# Simple_MCU_V01.net
KiCad netlist of a schematic drawn in EAGLE
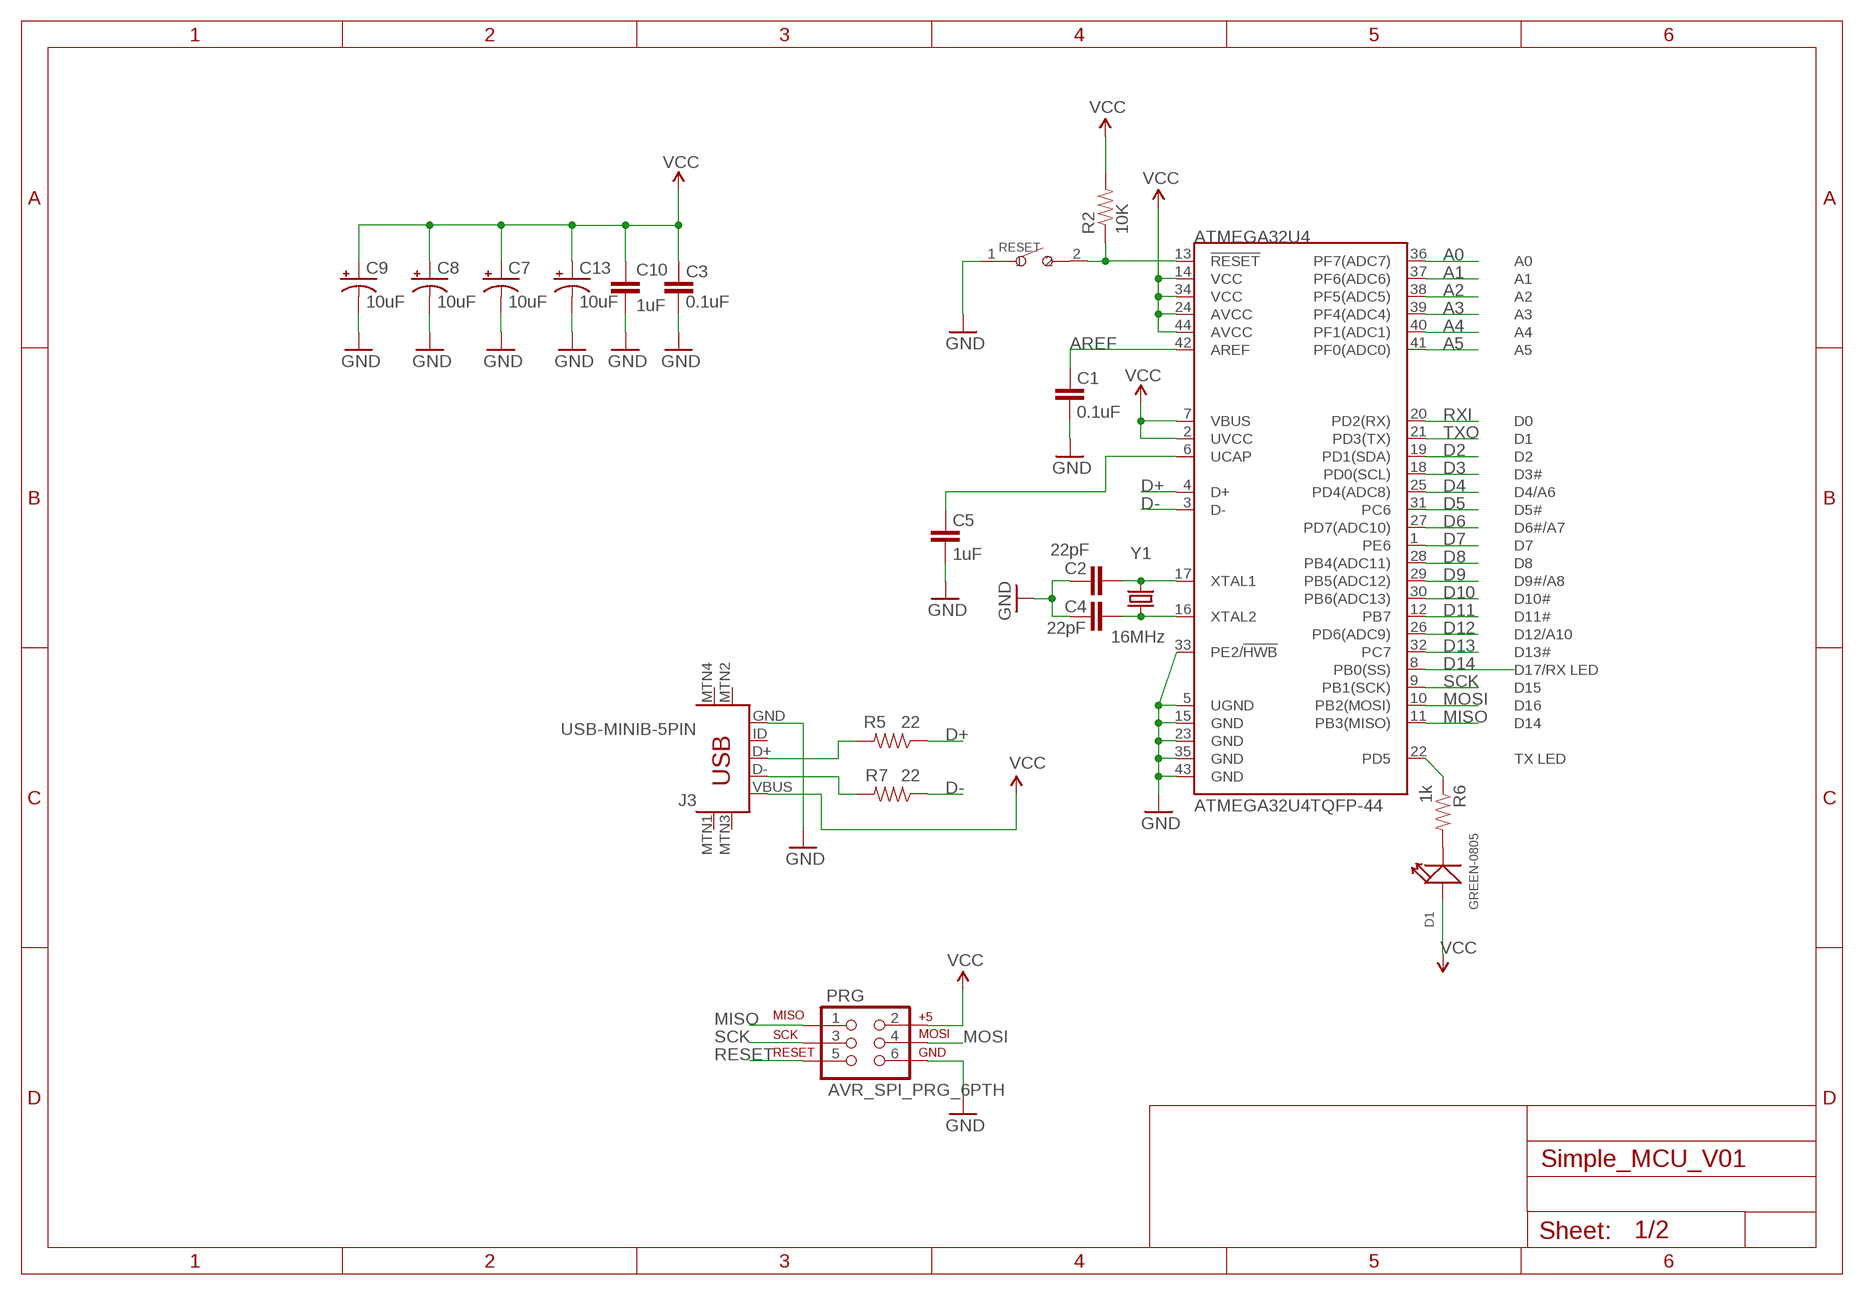
[diagram p0: schematic, sheet 1]
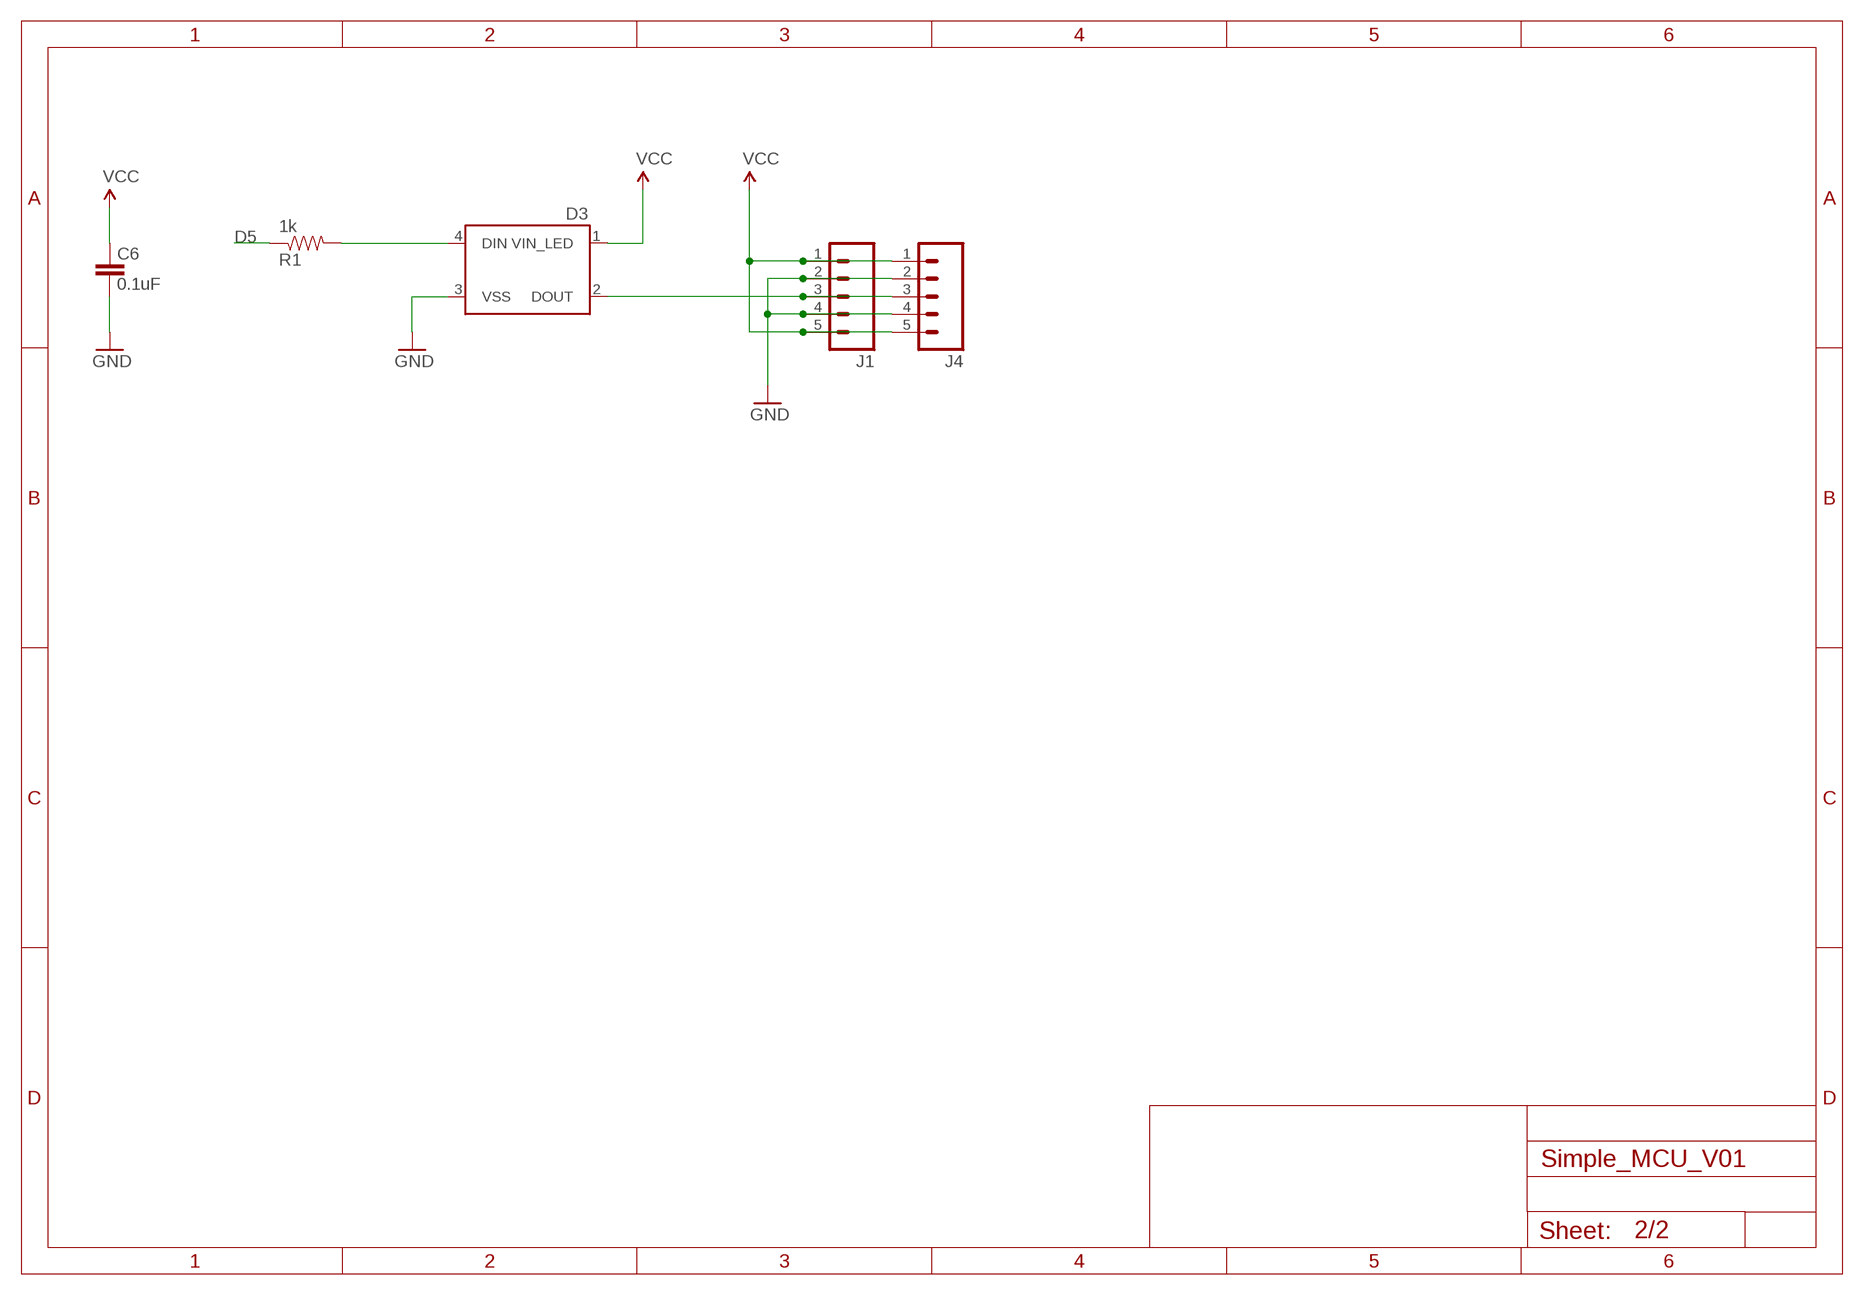
[diagram p1: schematic, sheet 2]

(export (version "E")
  (design (tool "Eeschema 10.0.6"))
  (components
    (comp (ref "ATMEGA32U4")
      (value "ATMEGA32U4TQFP-44")
      (footprint "eagle-import:TQFP44")
      (libsource (lib "eagle-import") (part "ATMEGA32U4TQFP-44"))
    )
    (comp (ref "C1")
      (value "0.1uF")
      (footprint "eagle-import:0805")
      (libsource (lib "eagle-import") (part "CAP0805"))
    )
    (comp (ref "C2")
      (value "22pF")
      (footprint "eagle-import:0805")
      (libsource (lib "eagle-import") (part "CAP0805"))
    )
    (comp (ref "C3")
      (value "0.1uF")
      (footprint "eagle-import:0805")
      (libsource (lib "eagle-import") (part "CAP0805"))
    )
    (comp (ref "C4")
      (value "22pF")
      (footprint "eagle-import:0805")
      (libsource (lib "eagle-import") (part "CAP0805"))
    )
    (comp (ref "C5")
      (value "1uF")
      (footprint "eagle-import:0805")
      (libsource (lib "eagle-import") (part "CAP0805"))
    )
    (comp (ref "C7")
      (value "10uF")
      (footprint "eagle-import:EIA3216")
      (libsource (lib "eagle-import") (part "CAP_POL1206"))
    )
    (comp (ref "C8")
      (value "10uF")
      (footprint "eagle-import:EIA3216")
      (libsource (lib "eagle-import") (part "CAP_POL1206"))
    )
    (comp (ref "C9")
      (value "10uF")
      (footprint "eagle-import:EIA3216")
      (libsource (lib "eagle-import") (part "CAP_POL1206"))
    )
    (comp (ref "C10")
      (value "1uF")
      (footprint "eagle-import:0805")
      (libsource (lib "eagle-import") (part "CAP0805"))
    )
    (comp (ref "C13")
      (value "10uF")
      (footprint "eagle-import:EIA3216")
      (libsource (lib "eagle-import") (part "CAP_POL1206"))
    )
    (comp (ref "D1")
      (value "GREEN-0805")
      (footprint "eagle-import:LED-0805")
      (fields (field (name "MPN") "17-215SYGC/S530-E2/TR8"))
      (libsource (lib "eagle-import") (part "SMD-LED-CLEAR-GREEN(0805)"))
    )
    (comp (ref "J3")
      (value "USB-MINIB-5PIN")
      (footprint "eagle-import:USB-MINIB")
      (libsource (lib "eagle-import") (part "USB-MINIB-5PIN"))
    )
    (comp (ref "PRG")
      (value "AVR_SPI_PRG_6PTH")
      (footprint "eagle-import:2X3")
      (libsource (lib "eagle-import") (part "AVR_SPI_PRG_6PTH"))
    )
    (comp (ref "R2")
      (value "10K")
      (footprint "eagle-import:0805")
      (libsource (lib "eagle-import") (part "RESISTOR0805-RES"))
    )
    (comp (ref "R5")
      (value "22")
      (footprint "eagle-import:0805")
      (libsource (lib "eagle-import") (part "RESISTOR0805-RES"))
    )
    (comp (ref "R6")
      (value "1k")
      (footprint "eagle-import:0805")
      (libsource (lib "eagle-import") (part "RESISTOR0805-RES"))
    )
    (comp (ref "R7")
      (value "22")
      (footprint "eagle-import:0805")
      (libsource (lib "eagle-import") (part "RESISTOR0805-RES"))
    )
    (comp (ref "RESET")
      (value "B3U-1000P-2P-SMD")
      (footprint "eagle-import:SW2-4.0X3.0X2.0")
      (libsource (lib "eagle-import") (part "SMD-BUTTON(2P-4.0X3.0X1.5+0.5MM)SW-TS-017A-2P"))
    )
    (comp (ref "Y1")
      (value "16MHz")
      (footprint "eagle-import:HC49US")
      (libsource (lib "eagle-import") (part "CRYSTALHC49US"))
    )
    (comp (ref "C6")
      (value "0.1uF")
      (footprint "eagle-import:0805")
      (libsource (lib "eagle-import") (part "CAP0805"))
    )
    (comp (ref "D3")
      (value "WS2812B")
      (footprint "eagle-import:WS2812B")
      (libsource (lib "eagle-import") (part "WS2812B"))
    )
    (comp (ref "J1")
      (value "M05NO_SILK")
      (footprint "eagle-import:1X05_NO_SILK")
      (libsource (lib "eagle-import") (part "M05NO_SILK"))
    )
    (comp (ref "J4")
      (value "M05PTH_LONGPADS")
      (footprint "eagle-import:1X05_LONGPADS")
      (libsource (lib "eagle-import") (part "M05PTH_LONGPADS"))
    )
    (comp (ref "R1")
      (value "1k")
      (footprint "eagle-import:0805")
      (libsource (lib "eagle-import") (part "RESISTOR0805-RES"))
    )
  )
  (nets
    (net (code "1") (name "3.3V") (class "Default")
      (node (ref "ATMEGA32U4") (pin "14") (pinfunction "VCC_14") (pintype "bidirectional"))
      (node (ref "ATMEGA32U4") (pin "2") (pinfunction "UVCC_2") (pintype "bidirectional"))
      (node (ref "ATMEGA32U4") (pin "24") (pinfunction "AVCC_24") (pintype "bidirectional"))
      (node (ref "ATMEGA32U4") (pin "34") (pinfunction "VCC_34") (pintype "bidirectional"))
      (node (ref "ATMEGA32U4") (pin "44") (pinfunction "AVCC_44") (pintype "bidirectional"))
      (node (ref "ATMEGA32U4") (pin "7") (pinfunction "VBUS_7") (pintype "bidirectional"))
      (node (ref "C10") (pin "1") (pinfunction "1_1") (pintype "passive"))
      (node (ref "C13") (pin "A") (pinfunction "+_A") (pintype "passive"))
      (node (ref "C3") (pin "2") (pinfunction "2_2") (pintype "passive"))
      (node (ref "C6") (pin "2") (pinfunction "2_2") (pintype "passive"))
      (node (ref "C7") (pin "A") (pinfunction "+_A") (pintype "passive"))
      (node (ref "C8") (pin "A") (pinfunction "+_A") (pintype "passive"))
      (node (ref "C9") (pin "A") (pinfunction "+_A") (pintype "passive"))
      (node (ref "D1") (pin "+") (pinfunction "+_+") (pintype "passive"))
      (node (ref "D3") (pin "1") (pinfunction "VIN_LED_1") (pintype "power_in"))
      (node (ref "J1") (pin "1") (pinfunction "1_1") (pintype "passive"))
      (node (ref "J1") (pin "5") (pinfunction "5_5") (pintype "passive"))
      (node (ref "J3") (pin "VBUS") (pinfunction "VBUS_VBUS") (pintype "bidirectional"))
      (node (ref "J4") (pin "1") (pinfunction "1_1") (pintype "passive"))
      (node (ref "J4") (pin "5") (pinfunction "5_5") (pintype "passive"))
      (node (ref "PRG") (pin "2") (pinfunction "2_2") (pintype "passive"))
      (node (ref "R2") (pin "2") (pinfunction "2_2") (pintype "passive"))
    )
    (net (code "2") (name "A0") (class "Default")
      (node (ref "ATMEGA32U4") (pin "36") (pinfunction "PF7(ADC7)_36") (pintype "bidirectional"))
    )
    (net (code "3") (name "A1") (class "Default")
      (node (ref "ATMEGA32U4") (pin "37") (pinfunction "PF6(ADC6)_37") (pintype "bidirectional"))
    )
    (net (code "4") (name "A2") (class "Default")
      (node (ref "ATMEGA32U4") (pin "38") (pinfunction "PF5(ADC5)_38") (pintype "bidirectional"))
    )
    (net (code "5") (name "A3") (class "Default")
      (node (ref "ATMEGA32U4") (pin "39") (pinfunction "PF4(ADC4)_39") (pintype "bidirectional"))
    )
    (net (code "6") (name "A4") (class "Default")
      (node (ref "ATMEGA32U4") (pin "40") (pinfunction "PF1(ADC1)_40") (pintype "bidirectional"))
    )
    (net (code "7") (name "A5") (class "Default")
      (node (ref "ATMEGA32U4") (pin "41") (pinfunction "PF0(ADC0)_41") (pintype "bidirectional"))
    )
    (net (code "8") (name "AREF") (class "Default")
      (node (ref "ATMEGA32U4") (pin "42") (pinfunction "AREF_42") (pintype "bidirectional"))
      (node (ref "C1") (pin "2") (pinfunction "2_2") (pintype "passive"))
    )
    (net (code "9") (name "D+") (class "Default")
      (node (ref "ATMEGA32U4") (pin "4") (pinfunction "D+_4") (pintype "bidirectional"))
      (node (ref "R5") (pin "1") (pinfunction "1_1") (pintype "passive"))
    )
    (net (code "10") (name "D-") (class "Default")
      (node (ref "ATMEGA32U4") (pin "3") (pinfunction "D-_3") (pintype "bidirectional"))
      (node (ref "R7") (pin "1") (pinfunction "1_1") (pintype "passive"))
    )
    (net (code "11") (name "D2") (class "Default")
      (node (ref "ATMEGA32U4") (pin "19") (pinfunction "PD1(SDA)_19") (pintype "bidirectional"))
    )
    (net (code "12") (name "D3") (class "Default")
      (node (ref "ATMEGA32U4") (pin "18") (pinfunction "PD0(SCL)_18") (pintype "bidirectional"))
    )
    (net (code "13") (name "D4") (class "Default")
      (node (ref "ATMEGA32U4") (pin "25") (pinfunction "PD4(ADC8)_25") (pintype "bidirectional"))
    )
    (net (code "14") (name "D5") (class "Default")
      (node (ref "ATMEGA32U4") (pin "31") (pinfunction "PC6_31") (pintype "bidirectional"))
      (node (ref "R1") (pin "1") (pinfunction "1_1") (pintype "passive"))
    )
    (net (code "15") (name "D6") (class "Default")
      (node (ref "ATMEGA32U4") (pin "27") (pinfunction "PD7(ADC10)_27") (pintype "bidirectional"))
    )
    (net (code "16") (name "D7") (class "Default")
      (node (ref "ATMEGA32U4") (pin "1") (pinfunction "PE6_1") (pintype "bidirectional"))
    )
    (net (code "17") (name "D8") (class "Default")
      (node (ref "ATMEGA32U4") (pin "28") (pinfunction "PB4(ADC11)_28") (pintype "bidirectional"))
    )
    (net (code "18") (name "D9") (class "Default")
      (node (ref "ATMEGA32U4") (pin "29") (pinfunction "PB5(ADC12)_29") (pintype "bidirectional"))
    )
    (net (code "19") (name "D10") (class "Default")
      (node (ref "ATMEGA32U4") (pin "30") (pinfunction "PB6(ADC13)_30") (pintype "bidirectional"))
    )
    (net (code "20") (name "D11") (class "Default")
      (node (ref "ATMEGA32U4") (pin "12") (pinfunction "PB7_12") (pintype "bidirectional"))
    )
    (net (code "21") (name "D12") (class "Default")
      (node (ref "ATMEGA32U4") (pin "26") (pinfunction "PD6(ADC9)_26") (pintype "bidirectional"))
    )
    (net (code "22") (name "D13") (class "Default")
      (node (ref "ATMEGA32U4") (pin "32") (pinfunction "PC7_32") (pintype "bidirectional"))
    )
    (net (code "23") (name "D14") (class "Default")
      (node (ref "ATMEGA32U4") (pin "8") (pinfunction "PB0(SS)_8") (pintype "bidirectional"))
    )
    (net (code "24") (name "GND") (class "Default")
      (node (ref "ATMEGA32U4") (pin "15") (pinfunction "GND_15") (pintype "bidirectional"))
      (node (ref "ATMEGA32U4") (pin "23") (pinfunction "GND_23") (pintype "bidirectional"))
      (node (ref "ATMEGA32U4") (pin "33") (pinfunction "PE2/~{HWB}_33") (pintype "bidirectional"))
      (node (ref "ATMEGA32U4") (pin "35") (pinfunction "GND_35") (pintype "bidirectional"))
      (node (ref "ATMEGA32U4") (pin "43") (pinfunction "GND_43") (pintype "bidirectional"))
      (node (ref "ATMEGA32U4") (pin "5") (pinfunction "UGND_5") (pintype "bidirectional"))
      (node (ref "C1") (pin "1") (pinfunction "1_1") (pintype "passive"))
      (node (ref "C10") (pin "2") (pinfunction "2_2") (pintype "passive"))
      (node (ref "C13") (pin "C") (pinfunction "-_C") (pintype "passive"))
      (node (ref "C2") (pin "2") (pinfunction "2_2") (pintype "passive"))
      (node (ref "C3") (pin "1") (pinfunction "1_1") (pintype "passive"))
      (node (ref "C4") (pin "2") (pinfunction "2_2") (pintype "passive"))
      (node (ref "C5") (pin "1") (pinfunction "1_1") (pintype "passive"))
      (node (ref "C6") (pin "1") (pinfunction "1_1") (pintype "passive"))
      (node (ref "C7") (pin "C") (pinfunction "-_C") (pintype "passive"))
      (node (ref "C8") (pin "C") (pinfunction "-_C") (pintype "passive"))
      (node (ref "C9") (pin "C") (pinfunction "-_C") (pintype "passive"))
      (node (ref "D3") (pin "3") (pinfunction "VSS_3") (pintype "power_in"))
      (node (ref "J1") (pin "2") (pinfunction "2_2") (pintype "passive"))
      (node (ref "J1") (pin "4") (pinfunction "4_4") (pintype "passive"))
      (node (ref "J3") (pin "GND") (pinfunction "GND_GND") (pintype "bidirectional"))
      (node (ref "J4") (pin "2") (pinfunction "2_2") (pintype "passive"))
      (node (ref "J4") (pin "4") (pinfunction "4_4") (pintype "passive"))
      (node (ref "PRG") (pin "6") (pinfunction "6_6") (pintype "passive"))
      (node (ref "RESET") (pin "1") (pinfunction "1_1") (pintype "bidirectional"))
    )
    (net (code "25") (name "MISO") (class "Default")
      (node (ref "ATMEGA32U4") (pin "11") (pinfunction "PB3(MISO)_11") (pintype "bidirectional"))
      (node (ref "PRG") (pin "1") (pinfunction "1_1") (pintype "passive"))
    )
    (net (code "26") (name "MOSI") (class "Default")
      (node (ref "ATMEGA32U4") (pin "10") (pinfunction "PB2(MOSI)_10") (pintype "bidirectional"))
      (node (ref "PRG") (pin "4") (pinfunction "4_4") (pintype "passive"))
    )
    (net (code "27") (name "Net-(ATMEGA32U4-PD5)") (class "Default")
      (node (ref "ATMEGA32U4") (pin "22") (pinfunction "PD5_22") (pintype "bidirectional"))
      (node (ref "R6") (pin "1") (pinfunction "1_1") (pintype "passive"))
    )
    (net (code "28") (name "Net-(ATMEGA32U4-UCAP)") (class "Default")
      (node (ref "ATMEGA32U4") (pin "6") (pinfunction "UCAP_6") (pintype "bidirectional"))
      (node (ref "C5") (pin "2") (pinfunction "2_2") (pintype "passive"))
    )
    (net (code "29") (name "Net-(ATMEGA32U4-XTAL1)") (class "Default")
      (node (ref "ATMEGA32U4") (pin "17") (pinfunction "XTAL1_17") (pintype "bidirectional"))
      (node (ref "C2") (pin "1") (pinfunction "1_1") (pintype "passive"))
      (node (ref "Y1") (pin "2") (pinfunction "2_2") (pintype "passive"))
    )
    (net (code "30") (name "Net-(ATMEGA32U4-XTAL2)") (class "Default")
      (node (ref "ATMEGA32U4") (pin "16") (pinfunction "XTAL2_16") (pintype "bidirectional"))
      (node (ref "C4") (pin "1") (pinfunction "1_1") (pintype "passive"))
      (node (ref "Y1") (pin "1") (pinfunction "1_1") (pintype "passive"))
    )
    (net (code "31") (name "Net-(D1-Pad-)") (class "Default")
      (node (ref "D1") (pin "-") (pinfunction "-_-") (pintype "passive"))
      (node (ref "R6") (pin "2") (pinfunction "2_2") (pintype "passive"))
    )
    (net (code "32") (name "Net-(D3-DIN)") (class "Default")
      (node (ref "D3") (pin "4") (pinfunction "DIN_4") (pintype "input"))
      (node (ref "R1") (pin "2") (pinfunction "2_2") (pintype "passive"))
    )
    (net (code "33") (name "Net-(D3-DOUT)") (class "Default")
      (node (ref "D3") (pin "2") (pinfunction "DOUT_2") (pintype "output"))
      (node (ref "J1") (pin "3") (pinfunction "3_3") (pintype "passive"))
      (node (ref "J4") (pin "3") (pinfunction "3_3") (pintype "passive"))
    )
    (net (code "34") (name "Net-(J3-PadD+)") (class "Default")
      (node (ref "J3") (pin "D+") (pinfunction "D+_D+") (pintype "bidirectional"))
      (node (ref "R5") (pin "2") (pinfunction "2_2") (pintype "passive"))
    )
    (net (code "35") (name "Net-(J3-PadD-)") (class "Default")
      (node (ref "J3") (pin "D-") (pinfunction "D-_D-") (pintype "bidirectional"))
      (node (ref "R7") (pin "2") (pinfunction "2_2") (pintype "passive"))
    )
    (net (code "36") (name "RESET") (class "Default")
      (node (ref "ATMEGA32U4") (pin "13") (pinfunction "~{RESET}_13") (pintype "bidirectional"))
      (node (ref "PRG") (pin "5") (pinfunction "5_5") (pintype "passive"))
      (node (ref "R2") (pin "1") (pinfunction "1_1") (pintype "passive"))
      (node (ref "RESET") (pin "2") (pinfunction "2_2") (pintype "bidirectional"))
    )
    (net (code "37") (name "RXI") (class "Default")
      (node (ref "ATMEGA32U4") (pin "20") (pinfunction "PD2(RX)_20") (pintype "bidirectional"))
    )
    (net (code "38") (name "SCK") (class "Default")
      (node (ref "ATMEGA32U4") (pin "9") (pinfunction "PB1(SCK)_9") (pintype "bidirectional"))
      (node (ref "PRG") (pin "3") (pinfunction "3_3") (pintype "passive"))
    )
    (net (code "39") (name "TXO") (class "Default")
      (node (ref "ATMEGA32U4") (pin "21") (pinfunction "PD3(TX)_21") (pintype "bidirectional"))
    )
    (net (code "40") (name "unconnected-(J3-MTN1-PadMTN3)") (class "Default")
      (node (ref "J3") (pin "MTN3") (pinfunction "MTN1_MTN3") (pintype "bidirectional"))
    )
    (net (code "41") (name "unconnected-(J3-MTN2-PadMTN1)") (class "Default")
      (node (ref "J3") (pin "MTN1") (pinfunction "MTN2_MTN1") (pintype "bidirectional"))
    )
    (net (code "42") (name "unconnected-(J3-MTN3-PadMTN2)") (class "Default")
      (node (ref "J3") (pin "MTN2") (pinfunction "MTN3_MTN2") (pintype "bidirectional"))
    )
    (net (code "43") (name "unconnected-(J3-PadID)") (class "Default")
      (node (ref "J3") (pin "ID") (pinfunction "ID_ID") (pintype "bidirectional"))
    )
    (net (code "44") (name "unconnected-(J3-PadMTN4)") (class "Default")
      (node (ref "J3") (pin "MTN4") (pinfunction "MTN4_MTN4") (pintype "bidirectional"))
    )
  )
)
